# yarns_v03.net
KiCad netlist of a schematic drawn in EAGLE
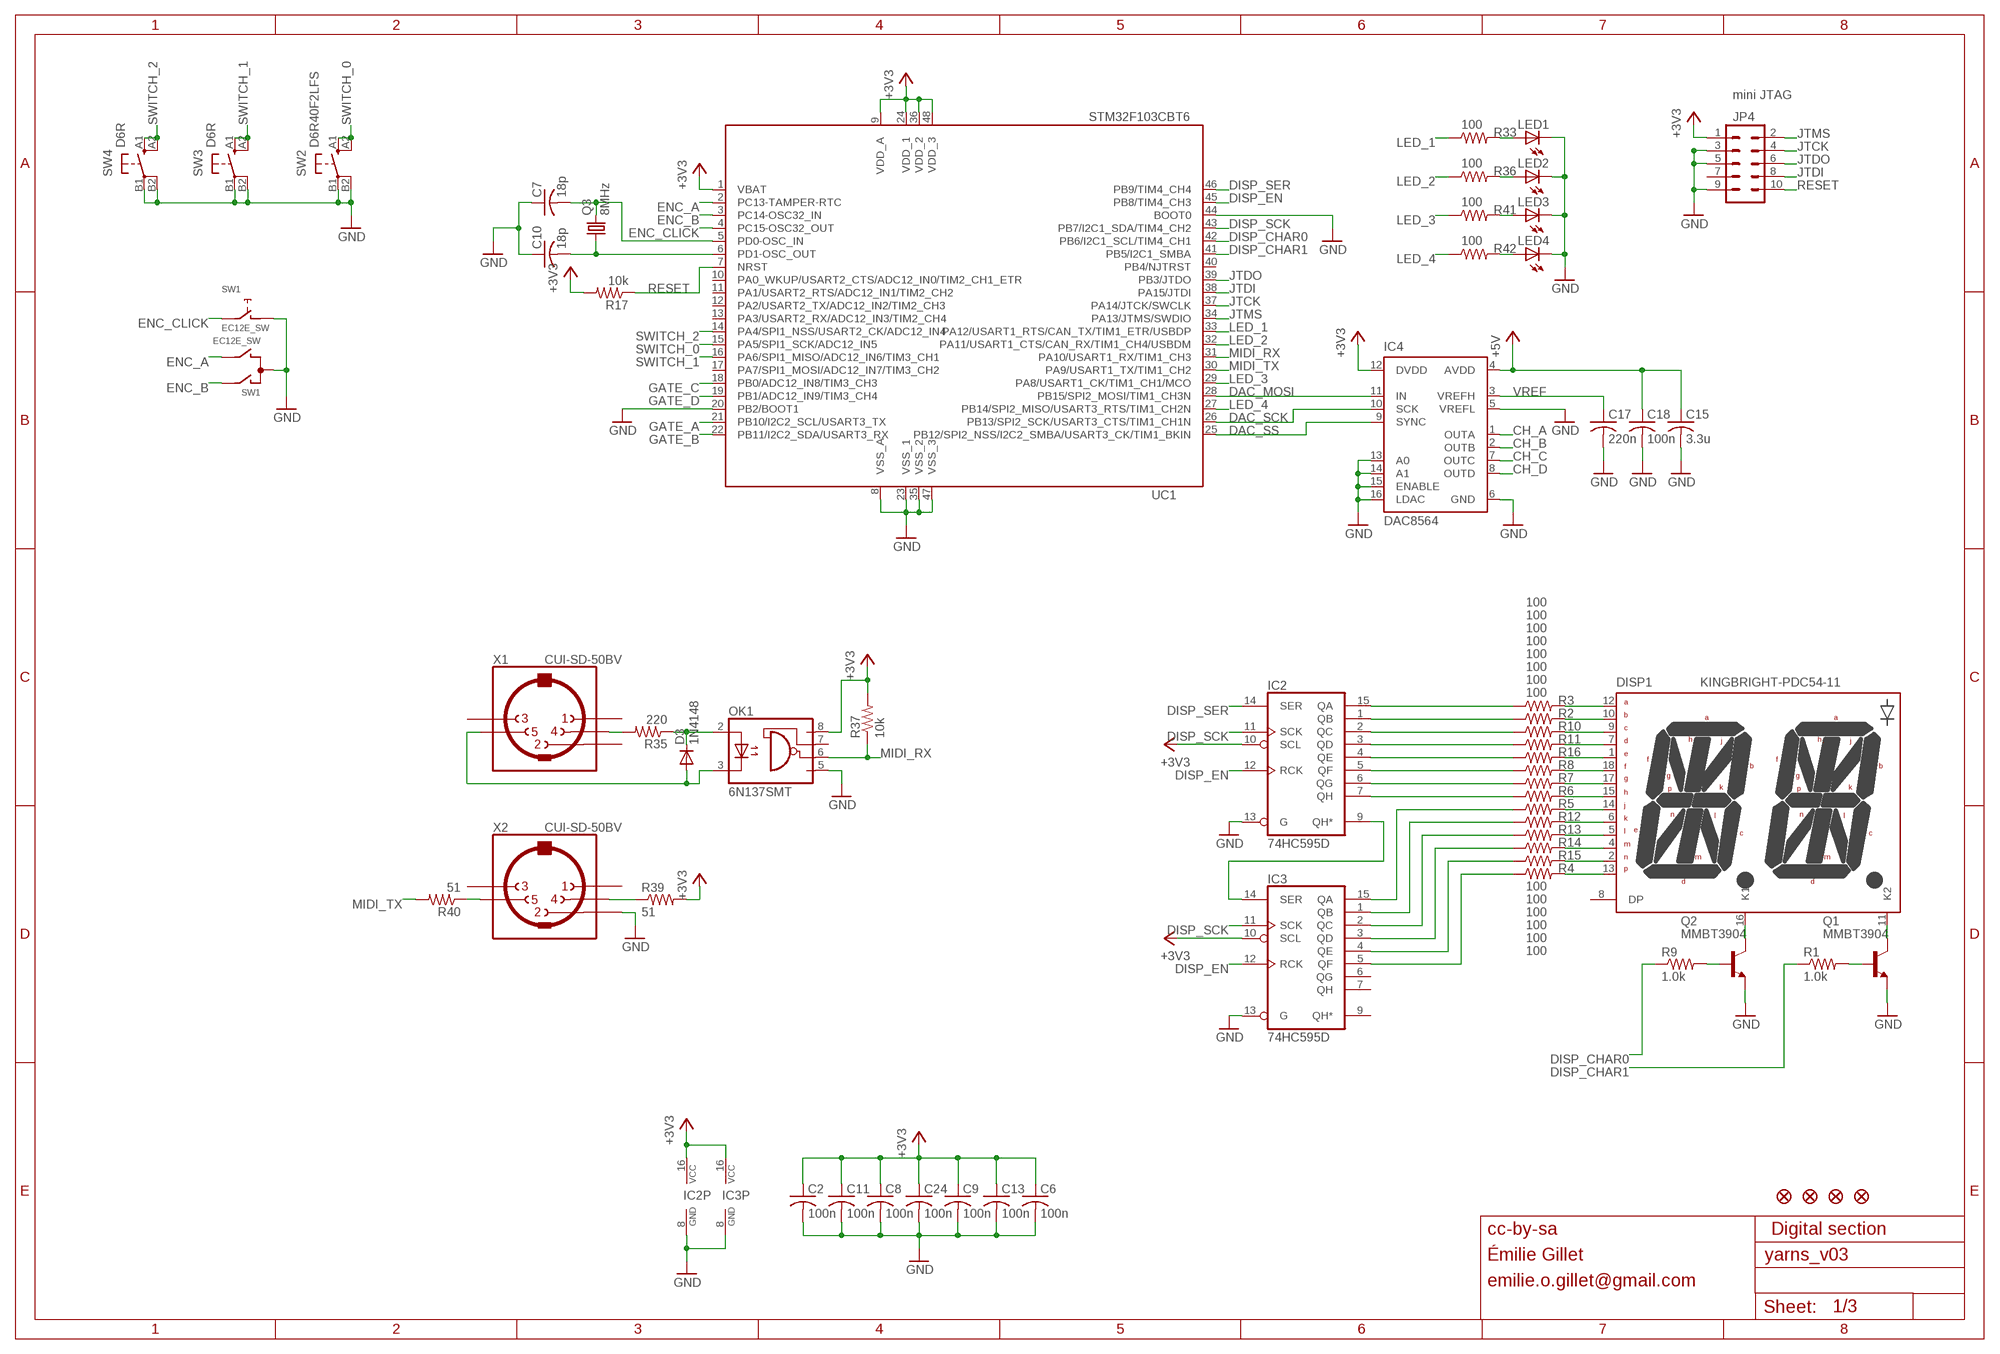
[diagram p0: schematic, sheet 1]
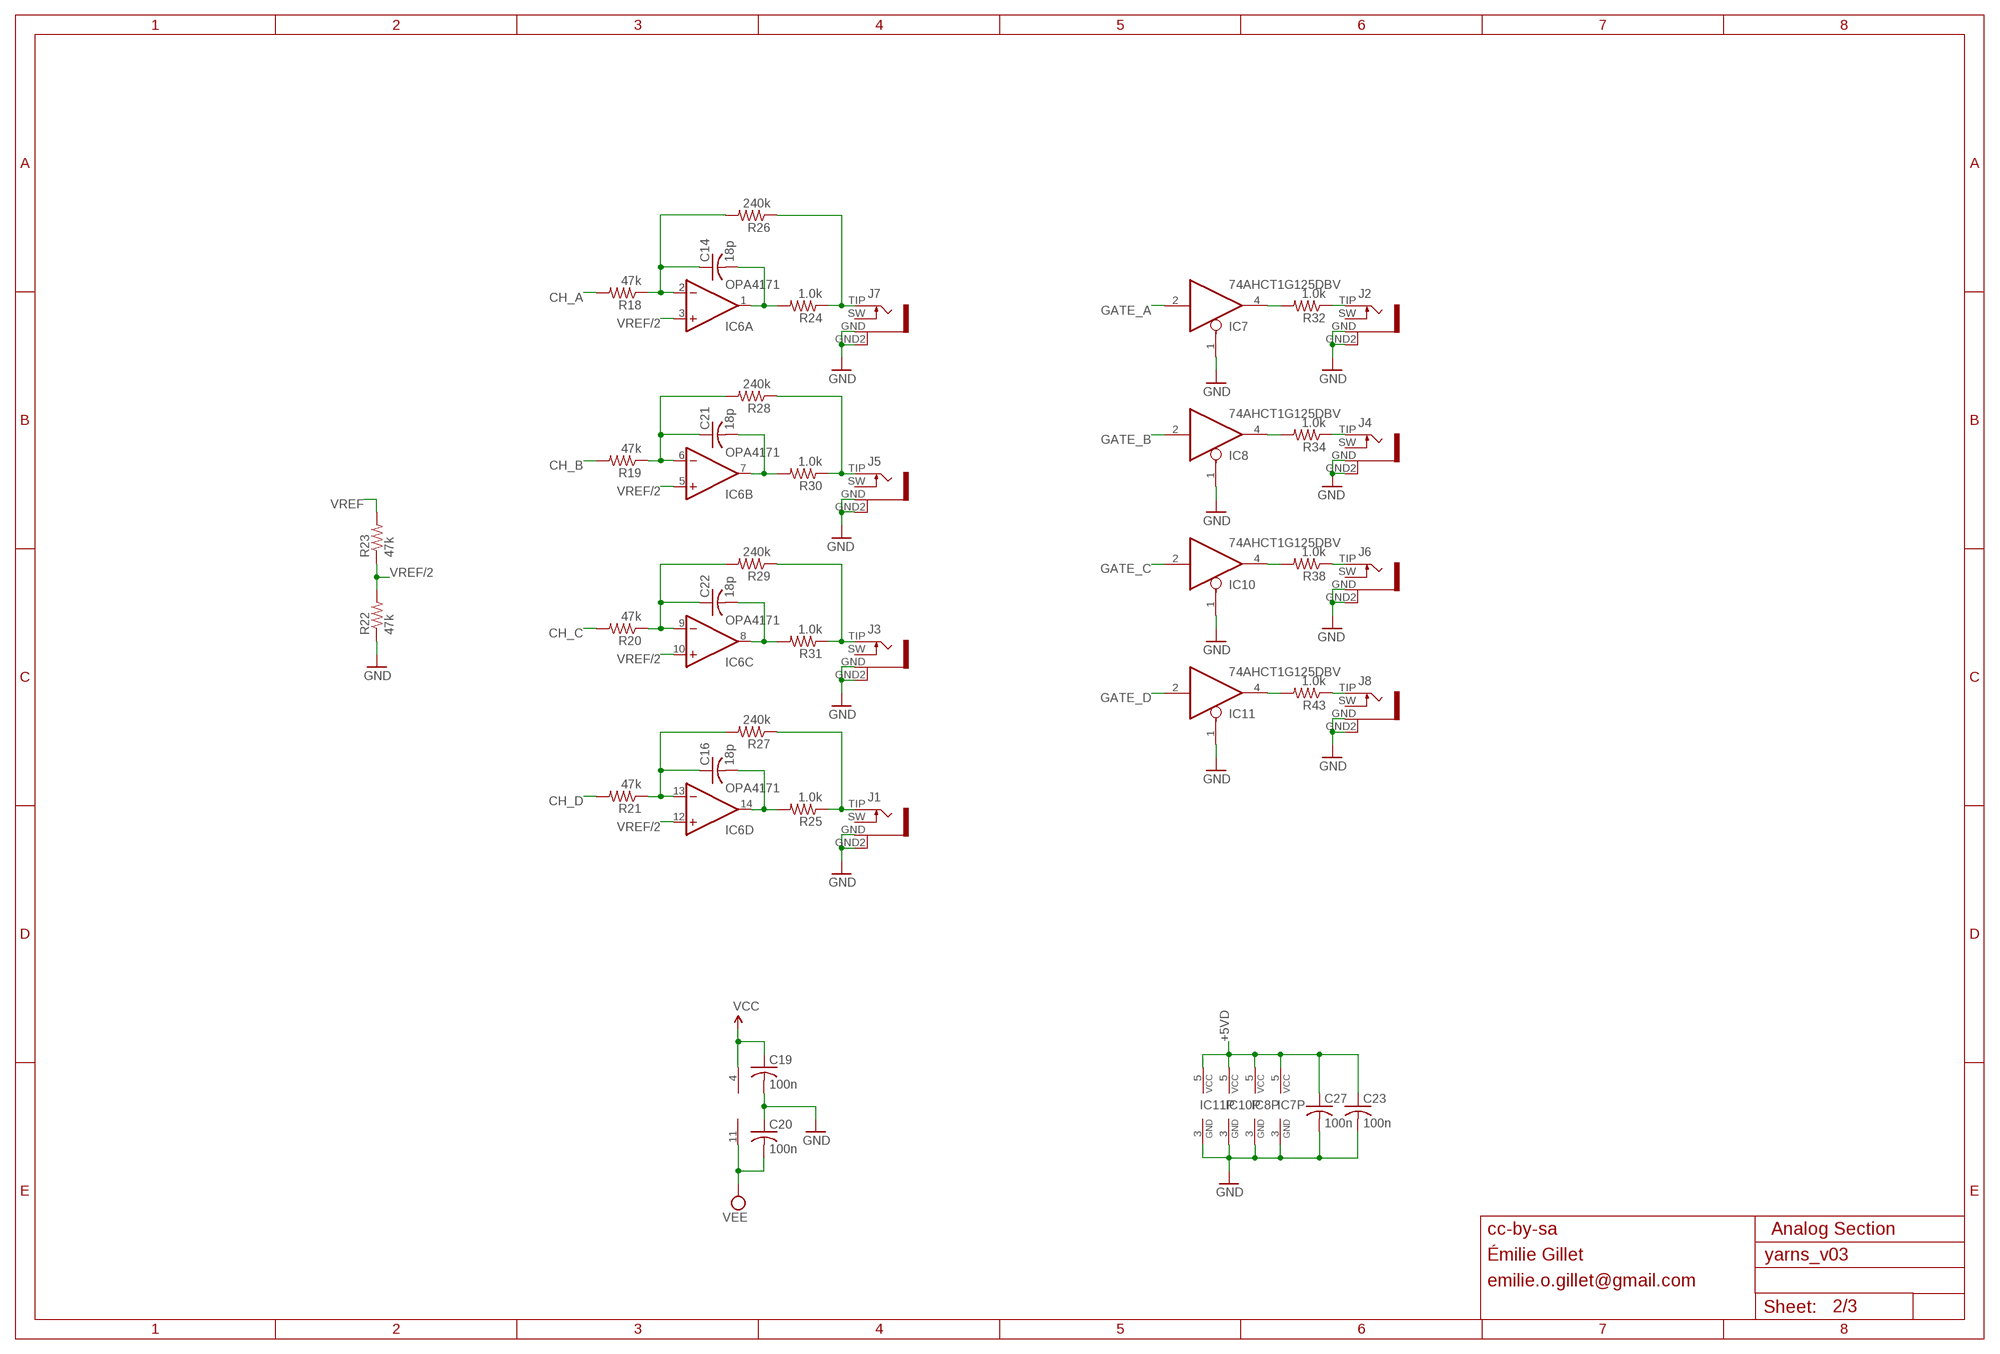
[diagram p1: schematic, sheet 2]
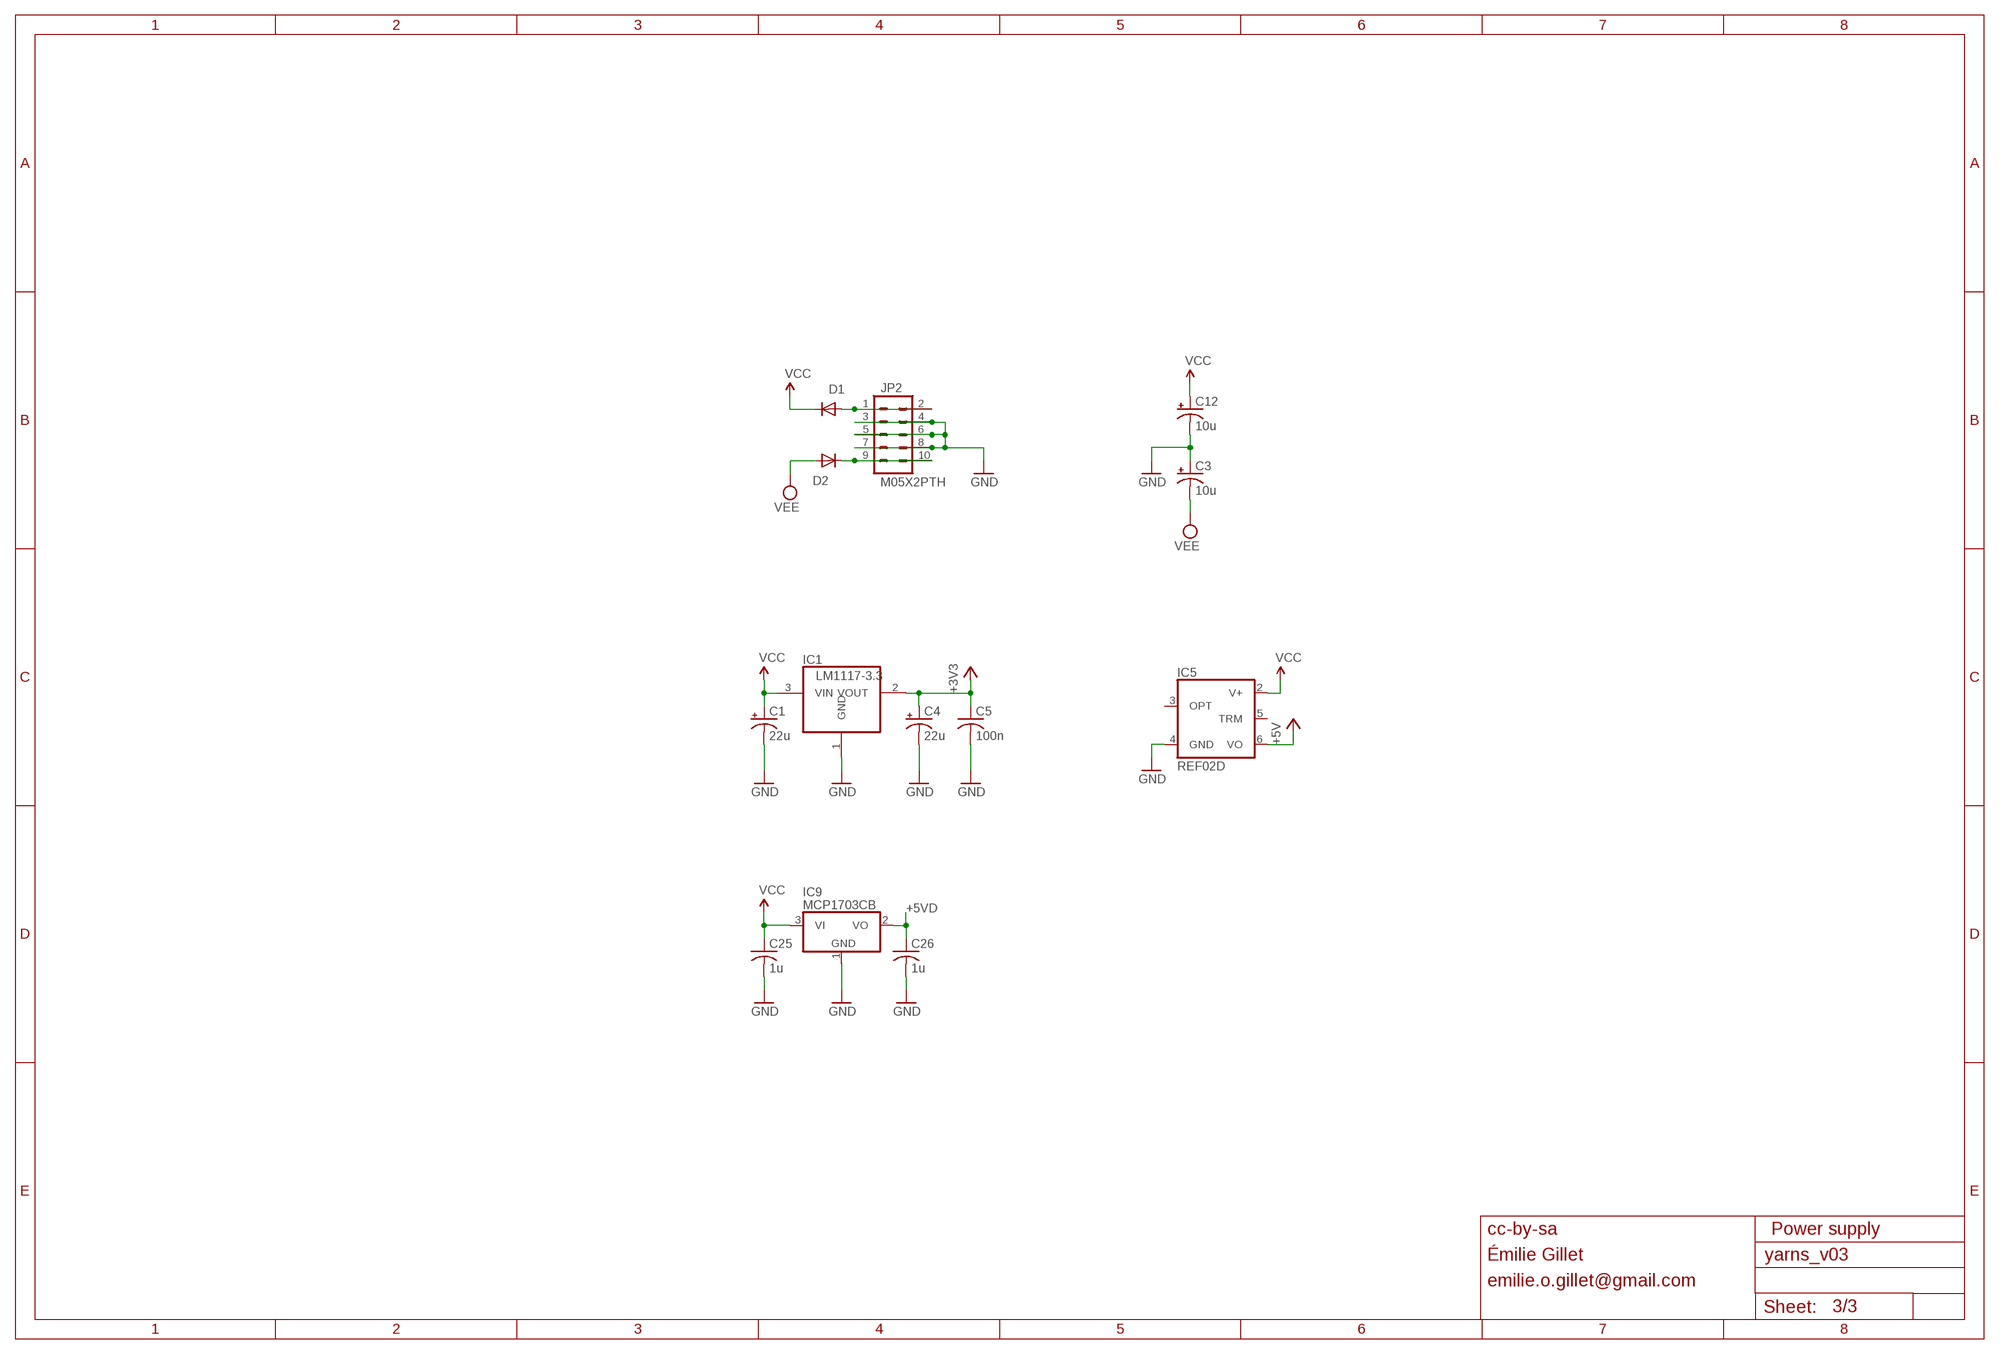
[diagram p2: schematic, sheet 3]

(export (version "E")
  (design (tool "Eeschema 10.0.6"))
  (components
    (comp (ref "C1")
      (value "22u")
      (footprint "eagle-import:PANASONIC_C")
      (libsource (lib "eagle-import") (part "CPOL-USC"))
    )
    (comp (ref "C3")
      (value "10u")
      (footprint "eagle-import:PANASONIC_A")
      (libsource (lib "eagle-import") (part "CPOL-USA"))
    )
    (comp (ref "C4")
      (value "22u")
      (footprint "eagle-import:PANASONIC_C")
      (libsource (lib "eagle-import") (part "CPOL-USC"))
    )
    (comp (ref "C5")
      (value "100n")
      (footprint "eagle-import:C0603")
      (libsource (lib "eagle-import") (part "C-USC0603"))
    )
    (comp (ref "C12")
      (value "10u")
      (footprint "eagle-import:PANASONIC_A")
      (libsource (lib "eagle-import") (part "CPOL-USA"))
    )
    (comp (ref "C25")
      (value "1u")
      (footprint "eagle-import:C0603")
      (libsource (lib "eagle-import") (part "C-USC0603"))
    )
    (comp (ref "C26")
      (value "1u")
      (footprint "eagle-import:C0603")
      (libsource (lib "eagle-import") (part "C-USC0603"))
    )
    (comp (ref "D1")
      (value "1N5819HW")
      (footprint "eagle-import:SOD123")
      (libsource (lib "eagle-import") (part "DIODE-SOD123"))
    )
    (comp (ref "D2")
      (value "1N5819HW")
      (footprint "eagle-import:SOD123")
      (libsource (lib "eagle-import") (part "DIODE-SOD123"))
    )
    (comp (ref "IC1")
      (value "LM1117-3.3")
      (footprint "eagle-import:SOT223")
      (libsource (lib "eagle-import") (part "REG1117"))
    )
    (comp (ref "IC5")
      (value "REF02D")
      (footprint "eagle-import:SO08")
      (libsource (lib "eagle-import") (part "REF02D"))
    )
    (comp (ref "IC9")
      (value "MCP1703CB")
      (footprint "eagle-import:SOT23")
      (libsource (lib "eagle-import") (part "MCP1703CB"))
    )
    (comp (ref "JP2")
      (value "M05X2PTH")
      (footprint "eagle-import:AVR_ICSP")
      (libsource (lib "eagle-import") (part "M05X2PTH"))
    )
    (comp (ref "C2")
      (value "100n")
      (footprint "eagle-import:C0603")
      (libsource (lib "eagle-import") (part "C-USC0603"))
    )
    (comp (ref "C6")
      (value "100n")
      (footprint "eagle-import:C0603")
      (libsource (lib "eagle-import") (part "C-USC0603"))
    )
    (comp (ref "C7")
      (value "18p")
      (footprint "eagle-import:C0603")
      (libsource (lib "eagle-import") (part "C-USC0603"))
    )
    (comp (ref "C8")
      (value "100n")
      (footprint "eagle-import:C0603")
      (libsource (lib "eagle-import") (part "C-USC0603"))
    )
    (comp (ref "C9")
      (value "100n")
      (footprint "eagle-import:C0603")
      (libsource (lib "eagle-import") (part "C-USC0603"))
    )
    (comp (ref "C10")
      (value "18p")
      (footprint "eagle-import:C0603")
      (libsource (lib "eagle-import") (part "C-USC0603"))
    )
    (comp (ref "C11")
      (value "100n")
      (footprint "eagle-import:C0603")
      (libsource (lib "eagle-import") (part "C-USC0603"))
    )
    (comp (ref "C13")
      (value "100n")
      (footprint "eagle-import:C0603")
      (libsource (lib "eagle-import") (part "C-USC0603"))
    )
    (comp (ref "C15")
      (value "3.3u")
      (footprint "eagle-import:C0603")
      (libsource (lib "eagle-import") (part "C-USC0603"))
    )
    (comp (ref "C17")
      (value "220n")
      (footprint "eagle-import:C0603")
      (libsource (lib "eagle-import") (part "C-USC0603"))
    )
    (comp (ref "C18")
      (value "100n")
      (footprint "eagle-import:C0603")
      (libsource (lib "eagle-import") (part "C-USC0603"))
    )
    (comp (ref "C24")
      (value "100n")
      (footprint "eagle-import:C0603")
      (libsource (lib "eagle-import") (part "C-USC0603"))
    )
    (comp (ref "D3")
      (value "1N4148")
      (footprint "eagle-import:SOD323-W")
      (libsource (lib "eagle-import") (part "DIODE-SOD323-W"))
    )
    (comp (ref "DISP1")
      (value "KINGBRIGHT-PDC54-11")
      (footprint "eagle-import:PDC54")
      (libsource (lib "eagle-import") (part "KINGBRIGHT-PDC54-11"))
    )
    (comp (ref "F1")
      (value "FIDUCIAL1X2")
      (footprint "eagle-import:FIDUCIAL-1X2")
      (libsource (lib "eagle-import") (part "FIDUCIAL1X2"))
    )
    (comp (ref "F3")
      (value "FIDUCIAL1X2")
      (footprint "eagle-import:FIDUCIAL-1X2")
      (libsource (lib "eagle-import") (part "FIDUCIAL1X2"))
    )
    (comp (ref "F5")
      (value "FIDUCIAL1X2")
      (footprint "eagle-import:FIDUCIAL-1X2")
      (libsource (lib "eagle-import") (part "FIDUCIAL1X2"))
    )
    (comp (ref "F6")
      (value "FIDUCIAL1X2")
      (footprint "eagle-import:FIDUCIAL-1X2")
      (libsource (lib "eagle-import") (part "FIDUCIAL1X2"))
    )
    (comp (ref "IC2")
      (value "74HC595D")
      (footprint "eagle-import:SO16")
      (libsource (lib "eagle-import") (part "74595DHC"))
    )
    (comp (ref "IC3")
      (value "74HC595D")
      (footprint "eagle-import:SO16")
      (libsource (lib "eagle-import") (part "74595DHC"))
    )
    (comp (ref "IC4")
      (value "DAC8564")
      (footprint "eagle-import:SOP65P640X110-16N")
      (libsource (lib "eagle-import") (part "DAC8564"))
    )
    (comp (ref "JP4")
      (value "M05X2MINIJTAG")
      (footprint "eagle-import:2X5-1.27")
      (libsource (lib "eagle-import") (part "M05X2MINIJTAG"))
    )
    (comp (ref "LED1")
      (value "LED3MM")
      (footprint "eagle-import:LED3MM")
      (libsource (lib "eagle-import") (part "LED3MM"))
    )
    (comp (ref "LED2")
      (value "LED3MM")
      (footprint "eagle-import:LED3MM")
      (libsource (lib "eagle-import") (part "LED3MM"))
    )
    (comp (ref "LED3")
      (value "LED3MM")
      (footprint "eagle-import:LED3MM")
      (libsource (lib "eagle-import") (part "LED3MM"))
    )
    (comp (ref "LED4")
      (value "LED3MM")
      (footprint "eagle-import:LED3MM")
      (libsource (lib "eagle-import") (part "LED3MM"))
    )
    (comp (ref "OK1")
      (value "6N137SMT")
      (footprint "eagle-import:DIL8-SMD")
      (libsource (lib "eagle-import") (part "6N137SMT"))
    )
    (comp (ref "Q1")
      (value "MMBT3904")
      (footprint "eagle-import:SOT23-BEC")
      (libsource (lib "eagle-import") (part "-NPN-SOT23-BECMMBT3904LT1"))
    )
    (comp (ref "Q2")
      (value "MMBT3904")
      (footprint "eagle-import:SOT23-BEC")
      (libsource (lib "eagle-import") (part "-NPN-SOT23-BECMMBT3904LT1"))
    )
    (comp (ref "Q3")
      (value "8MHz")
      (footprint "eagle-import:HC49UP")
      (libsource (lib "eagle-import") (part "CRYSTALHC49UP"))
    )
    (comp (ref "R1")
      (value "1.0k")
      (footprint "eagle-import:R0603")
      (libsource (lib "eagle-import") (part "R-US_R0603"))
    )
    (comp (ref "R2")
      (value "100")
      (footprint "eagle-import:R0603")
      (libsource (lib "eagle-import") (part "R-US_R0603"))
    )
    (comp (ref "R3")
      (value "100")
      (footprint "eagle-import:R0603")
      (libsource (lib "eagle-import") (part "R-US_R0603"))
    )
    (comp (ref "R4")
      (value "100")
      (footprint "eagle-import:R0603")
      (libsource (lib "eagle-import") (part "R-US_R0603"))
    )
    (comp (ref "R5")
      (value "100")
      (footprint "eagle-import:R0603")
      (libsource (lib "eagle-import") (part "R-US_R0603"))
    )
    (comp (ref "R6")
      (value "100")
      (footprint "eagle-import:R0603")
      (libsource (lib "eagle-import") (part "R-US_R0603"))
    )
    (comp (ref "R7")
      (value "100")
      (footprint "eagle-import:R0603")
      (libsource (lib "eagle-import") (part "R-US_R0603"))
    )
    (comp (ref "R8")
      (value "100")
      (footprint "eagle-import:R0603")
      (libsource (lib "eagle-import") (part "R-US_R0603"))
    )
    (comp (ref "R9")
      (value "1.0k")
      (footprint "eagle-import:R0603")
      (libsource (lib "eagle-import") (part "R-US_R0603"))
    )
    (comp (ref "R10")
      (value "100")
      (footprint "eagle-import:R0603")
      (libsource (lib "eagle-import") (part "R-US_R0603"))
    )
    (comp (ref "R11")
      (value "100")
      (footprint "eagle-import:R0603")
      (libsource (lib "eagle-import") (part "R-US_R0603"))
    )
    (comp (ref "R12")
      (value "100")
      (footprint "eagle-import:R0603")
      (libsource (lib "eagle-import") (part "R-US_R0603"))
    )
    (comp (ref "R13")
      (value "100")
      (footprint "eagle-import:R0603")
      (libsource (lib "eagle-import") (part "R-US_R0603"))
    )
    (comp (ref "R14")
      (value "100")
      (footprint "eagle-import:R0603")
      (libsource (lib "eagle-import") (part "R-US_R0603"))
    )
    (comp (ref "R15")
      (value "100")
      (footprint "eagle-import:R0603")
      (libsource (lib "eagle-import") (part "R-US_R0603"))
    )
    (comp (ref "R16")
      (value "100")
      (footprint "eagle-import:R0603")
      (libsource (lib "eagle-import") (part "R-US_R0603"))
    )
    (comp (ref "R17")
      (value "10k")
      (footprint "eagle-import:R0603")
      (libsource (lib "eagle-import") (part "R-US_R0603"))
    )
    (comp (ref "R33")
      (value "100")
      (footprint "eagle-import:R0603")
      (libsource (lib "eagle-import") (part "R-US_R0603"))
    )
    (comp (ref "R35")
      (value "220")
      (footprint "eagle-import:R0603")
      (libsource (lib "eagle-import") (part "R-US_R0603"))
    )
    (comp (ref "R36")
      (value "100")
      (footprint "eagle-import:R0603")
      (libsource (lib "eagle-import") (part "R-US_R0603"))
    )
    (comp (ref "R37")
      (value "10k")
      (footprint "eagle-import:R0603")
      (libsource (lib "eagle-import") (part "R-US_R0603"))
    )
    (comp (ref "R39")
      (value "51")
      (footprint "eagle-import:R0603")
      (libsource (lib "eagle-import") (part "R-US_R0603"))
    )
    (comp (ref "R40")
      (value "51")
      (footprint "eagle-import:R0603")
      (libsource (lib "eagle-import") (part "R-US_R0603"))
    )
    (comp (ref "R41")
      (value "100")
      (footprint "eagle-import:R0603")
      (libsource (lib "eagle-import") (part "R-US_R0603"))
    )
    (comp (ref "R42")
      (value "100")
      (footprint "eagle-import:R0603")
      (libsource (lib "eagle-import") (part "R-US_R0603"))
    )
    (comp (ref "SW1")
      (value "EC12E_SW")
      (footprint "eagle-import:ALPS_EC12E_SW")
      (libsource (lib "eagle-import") (part "EC12E_SW"))
    )
    (comp (ref "SW2")
      (value "D6R40F2LFS")
      (footprint "eagle-import:D6R")
      (libsource (lib "eagle-import") (part "D6R"))
    )
    (comp (ref "SW3")
      (value "D6R")
      (footprint "eagle-import:D6R")
      (libsource (lib "eagle-import") (part "D6R"))
    )
    (comp (ref "SW4")
      (value "D6R")
      (footprint "eagle-import:D6R")
      (libsource (lib "eagle-import") (part "D6R"))
    )
    (comp (ref "UC1")
      (value "STM32F103CBT6")
      (footprint "eagle-import:LQFP48")
      (libsource (lib "eagle-import") (part "STM32F103CB"))
    )
    (comp (ref "X1")
      (value "CUI-SD-50BV")
      (footprint "eagle-import:SD-50BV")
      (libsource (lib "eagle-import") (part "MAB5SHCUI-SD-50BV"))
    )
    (comp (ref "X2")
      (value "CUI-SD-50BV")
      (footprint "eagle-import:SD-50BV")
      (libsource (lib "eagle-import") (part "MAB5SHCUI-SD-50BV"))
    )
    (comp (ref "C14")
      (value "18p")
      (footprint "eagle-import:C0603")
      (libsource (lib "eagle-import") (part "C-USC0603"))
    )
    (comp (ref "C16")
      (value "18p")
      (footprint "eagle-import:C0603")
      (libsource (lib "eagle-import") (part "C-USC0603"))
    )
    (comp (ref "C19")
      (value "100n")
      (footprint "eagle-import:C0603")
      (libsource (lib "eagle-import") (part "C-USC0603"))
    )
    (comp (ref "C20")
      (value "100n")
      (footprint "eagle-import:C0603")
      (libsource (lib "eagle-import") (part "C-USC0603"))
    )
    (comp (ref "C21")
      (value "18p")
      (footprint "eagle-import:C0603")
      (libsource (lib "eagle-import") (part "C-USC0603"))
    )
    (comp (ref "C22")
      (value "18p")
      (footprint "eagle-import:C0603")
      (libsource (lib "eagle-import") (part "C-USC0603"))
    )
    (comp (ref "C23")
      (value "100n")
      (footprint "eagle-import:C0603")
      (libsource (lib "eagle-import") (part "C-USC0603"))
    )
    (comp (ref "C27")
      (value "100n")
      (footprint "eagle-import:C0603")
      (libsource (lib "eagle-import") (part "C-USC0603"))
    )
    (comp (ref "IC6")
      (value "OPA4171")
      (footprint "eagle-import:SO14")
      (libsource (lib "eagle-import") (part "TL074D"))
    )
    (comp (ref "IC7")
      (value "74AHCT1G125DBV")
      (footprint "eagle-import:SOT23-5")
      (libsource (lib "eagle-import") (part "741G125DBVAHCT"))
    )
    (comp (ref "IC8")
      (value "74AHCT1G125DBV")
      (footprint "eagle-import:SOT23-5")
      (libsource (lib "eagle-import") (part "741G125DBVAHCT"))
    )
    (comp (ref "IC10")
      (value "74AHCT1G125DBV")
      (footprint "eagle-import:SOT23-5")
      (libsource (lib "eagle-import") (part "741G125DBVAHCT"))
    )
    (comp (ref "IC11")
      (value "74AHCT1G125DBV")
      (footprint "eagle-import:SOT23-5")
      (libsource (lib "eagle-import") (part "741G125DBVAHCT"))
    )
    (comp (ref "J1")
      (value "PJ301WQP")
      (footprint "eagle-import:WQP_PJ_301BM")
      (libsource (lib "eagle-import") (part "PJ301WQP"))
    )
    (comp (ref "J2")
      (value "PJ301WQP")
      (footprint "eagle-import:WQP_PJ_301BM")
      (libsource (lib "eagle-import") (part "PJ301WQP"))
    )
    (comp (ref "J3")
      (value "PJ301WQP")
      (footprint "eagle-import:WQP_PJ_301BM")
      (libsource (lib "eagle-import") (part "PJ301WQP"))
    )
    (comp (ref "J4")
      (value "PJ301WQP")
      (footprint "eagle-import:WQP_PJ_301BM")
      (libsource (lib "eagle-import") (part "PJ301WQP"))
    )
    (comp (ref "J5")
      (value "PJ301WQP")
      (footprint "eagle-import:WQP_PJ_301BM")
      (libsource (lib "eagle-import") (part "PJ301WQP"))
    )
    (comp (ref "J6")
      (value "PJ301WQP")
      (footprint "eagle-import:WQP_PJ_301BM")
      (libsource (lib "eagle-import") (part "PJ301WQP"))
    )
    (comp (ref "J7")
      (value "PJ301WQP")
      (footprint "eagle-import:WQP_PJ_301BM")
      (libsource (lib "eagle-import") (part "PJ301WQP"))
    )
    (comp (ref "J8")
      (value "PJ301WQP")
      (footprint "eagle-import:WQP_PJ_301BM")
      (libsource (lib "eagle-import") (part "PJ301WQP"))
    )
    (comp (ref "R18")
      (value "47k")
      (footprint "eagle-import:R0603")
      (libsource (lib "eagle-import") (part "R-US_R0603"))
    )
    (comp (ref "R19")
      (value "47k")
      (footprint "eagle-import:R0603")
      (libsource (lib "eagle-import") (part "R-US_R0603"))
    )
    (comp (ref "R20")
      (value "47k")
      (footprint "eagle-import:R0603")
      (libsource (lib "eagle-import") (part "R-US_R0603"))
    )
    (comp (ref "R21")
      (value "47k")
      (footprint "eagle-import:R0603")
      (libsource (lib "eagle-import") (part "R-US_R0603"))
    )
    (comp (ref "R22")
      (value "47k")
      (footprint "eagle-import:R0603")
      (libsource (lib "eagle-import") (part "R-US_R0603"))
    )
    (comp (ref "R23")
      (value "47k")
      (footprint "eagle-import:R0603")
      (libsource (lib "eagle-import") (part "R-US_R0603"))
    )
    (comp (ref "R24")
      (value "1.0k")
      (footprint "eagle-import:R0603")
      (libsource (lib "eagle-import") (part "R-US_R0603"))
    )
    (comp (ref "R25")
      (value "1.0k")
      (footprint "eagle-import:R0603")
      (libsource (lib "eagle-import") (part "R-US_R0603"))
    )
    (comp (ref "R26")
      (value "240k")
      (footprint "eagle-import:R0603")
      (libsource (lib "eagle-import") (part "R-US_R0603"))
    )
    (comp (ref "R27")
      (value "240k")
      (footprint "eagle-import:R0603")
      (libsource (lib "eagle-import") (part "R-US_R0603"))
    )
    (comp (ref "R28")
      (value "240k")
      (footprint "eagle-import:R0603")
      (libsource (lib "eagle-import") (part "R-US_R0603"))
    )
    (comp (ref "R29")
      (value "240k")
      (footprint "eagle-import:R0603")
      (libsource (lib "eagle-import") (part "R-US_R0603"))
    )
    (comp (ref "R30")
      (value "1.0k")
      (footprint "eagle-import:R0603")
      (libsource (lib "eagle-import") (part "R-US_R0603"))
    )
    (comp (ref "R31")
      (value "1.0k")
      (footprint "eagle-import:R0603")
      (libsource (lib "eagle-import") (part "R-US_R0603"))
    )
    (comp (ref "R32")
      (value "1.0k")
      (footprint "eagle-import:R0603")
      (libsource (lib "eagle-import") (part "R-US_R0603"))
    )
    (comp (ref "R34")
      (value "1.0k")
      (footprint "eagle-import:R0603")
      (libsource (lib "eagle-import") (part "R-US_R0603"))
    )
    (comp (ref "R38")
      (value "1.0k")
      (footprint "eagle-import:R0603")
      (libsource (lib "eagle-import") (part "R-US_R0603"))
    )
    (comp (ref "R43")
      (value "1.0k")
      (footprint "eagle-import:R0603")
      (libsource (lib "eagle-import") (part "R-US_R0603"))
    )
  )
  (nets
    (net (code "1") (name "+3V3") (class "Default")
      (node (ref "C11") (pin "1") (pinfunction "1_1") (pintype "passive"))
      (node (ref "C13") (pin "1") (pinfunction "1_1") (pintype "passive"))
      (node (ref "C2") (pin "1") (pinfunction "1_1") (pintype "passive"))
      (node (ref "C24") (pin "1") (pinfunction "1_1") (pintype "passive"))
      (node (ref "C4") (pin "+") (pinfunction "+_+") (pintype "passive"))
      (node (ref "C5") (pin "1") (pinfunction "1_1") (pintype "passive"))
      (node (ref "C6") (pin "1") (pinfunction "1_1") (pintype "passive"))
      (node (ref "C8") (pin "1") (pinfunction "1_1") (pintype "passive"))
      (node (ref "C9") (pin "1") (pinfunction "1_1") (pintype "passive"))
      (node (ref "IC1") (pin "2") (pinfunction "VOUT_2") (pintype "output"))
      (node (ref "IC2") (pin "10") (pinfunction "SCL_10") (pintype "input"))
      (node (ref "IC2") (pin "16") (pinfunction "VCC_16") (pintype "power_in"))
      (node (ref "IC3") (pin "10") (pinfunction "SCL_10") (pintype "input"))
      (node (ref "IC3") (pin "16") (pinfunction "VCC_16") (pintype "power_in"))
      (node (ref "IC4") (pin "12") (pinfunction "DVDD_12") (pintype "power_in"))
      (node (ref "JP4") (pin "1") (pinfunction "1_1") (pintype "passive"))
      (node (ref "OK1") (pin "8") (pinfunction "VCC_8") (pintype "passive"))
      (node (ref "R17") (pin "2") (pinfunction "2_2") (pintype "passive"))
      (node (ref "R37") (pin "2") (pinfunction "2_2") (pintype "passive"))
      (node (ref "R39") (pin "2") (pinfunction "2_2") (pintype "passive"))
      (node (ref "UC1") (pin "1") (pinfunction "VBAT_1") (pintype "power_in"))
      (node (ref "UC1") (pin "24") (pinfunction "VDD_1_24") (pintype "power_in"))
      (node (ref "UC1") (pin "36") (pinfunction "VDD_2_36") (pintype "power_in"))
      (node (ref "UC1") (pin "48") (pinfunction "VDD_3_48") (pintype "power_in"))
      (node (ref "UC1") (pin "9") (pinfunction "VDD_A_9") (pintype "power_in"))
    )
    (net (code "2") (name "+5V") (class "Default")
      (node (ref "C15") (pin "1") (pinfunction "1_1") (pintype "passive"))
      (node (ref "C18") (pin "1") (pinfunction "1_1") (pintype "passive"))
      (node (ref "IC4") (pin "4") (pinfunction "AVDD_4") (pintype "power_in"))
      (node (ref "IC5") (pin "6") (pinfunction "VO_6") (pintype "output"))
    )
    (net (code "3") (name "+5VD") (class "Default")
      (node (ref "C23") (pin "1") (pinfunction "1_1") (pintype "passive"))
      (node (ref "C26") (pin "1") (pinfunction "1_1") (pintype "passive"))
      (node (ref "C27") (pin "1") (pinfunction "1_1") (pintype "passive"))
      (node (ref "IC10") (pin "5") (pinfunction "VCC_5") (pintype "power_in"))
      (node (ref "IC11") (pin "5") (pinfunction "VCC_5") (pintype "power_in"))
      (node (ref "IC7") (pin "5") (pinfunction "VCC_5") (pintype "power_in"))
      (node (ref "IC8") (pin "5") (pinfunction "VCC_5") (pintype "power_in"))
      (node (ref "IC9") (pin "2") (pinfunction "VO_2") (pintype "passive"))
    )
    (net (code "4") (name "CH_A") (class "Default")
      (node (ref "IC4") (pin "1") (pinfunction "OUTA_1") (pintype "output"))
      (node (ref "R18") (pin "2") (pinfunction "2_2") (pintype "passive"))
    )
    (net (code "5") (name "CH_B") (class "Default")
      (node (ref "IC4") (pin "2") (pinfunction "OUTB_2") (pintype "output"))
      (node (ref "R19") (pin "2") (pinfunction "2_2") (pintype "passive"))
    )
    (net (code "6") (name "CH_C") (class "Default")
      (node (ref "IC4") (pin "7") (pinfunction "OUTC_7") (pintype "output"))
      (node (ref "R20") (pin "2") (pinfunction "2_2") (pintype "passive"))
    )
    (net (code "7") (name "CH_D") (class "Default")
      (node (ref "IC4") (pin "8") (pinfunction "OUTD_8") (pintype "output"))
      (node (ref "R21") (pin "2") (pinfunction "2_2") (pintype "passive"))
    )
    (net (code "8") (name "DAC_MOSI") (class "Default")
      (node (ref "IC4") (pin "11") (pinfunction "IN_11") (pintype "input"))
      (node (ref "UC1") (pin "28") (pinfunction "PB15/SPI2_MOSI/TIM1_CH3N_28") (pintype "input"))
    )
    (net (code "9") (name "DAC_SCK") (class "Default")
      (node (ref "IC4") (pin "10") (pinfunction "SCK_10") (pintype "input"))
      (node (ref "UC1") (pin "26") (pinfunction "PB13/SPI2_SCK/USART3_CTS/TIM1_CH1N_26") (pintype "input"))
    )
    (net (code "10") (name "DAC_SS") (class "Default")
      (node (ref "IC4") (pin "9") (pinfunction "SYNC_9") (pintype "input"))
      (node (ref "UC1") (pin "25") (pinfunction "PB12/SPI2_NSS/I2C2_SMBA/USART3_CK/TIM1_BKIN_25") (pintype "input"))
    )
    (net (code "11") (name "DISP_CHAR0") (class "Default")
      (node (ref "R9") (pin "1") (pinfunction "1_1") (pintype "passive"))
      (node (ref "UC1") (pin "42") (pinfunction "PB6/I2C1_SCL/TIM4_CH1_42") (pintype "input"))
    )
    (net (code "12") (name "DISP_CHAR1") (class "Default")
      (node (ref "R1") (pin "1") (pinfunction "1_1") (pintype "passive"))
      (node (ref "UC1") (pin "41") (pinfunction "PB5/I2C1_SMBA_41") (pintype "input"))
    )
    (net (code "13") (name "DISP_EN") (class "Default")
      (node (ref "IC2") (pin "12") (pinfunction "RCK_12") (pintype "input"))
      (node (ref "IC3") (pin "12") (pinfunction "RCK_12") (pintype "input"))
      (node (ref "UC1") (pin "45") (pinfunction "PB8/TIM4_CH3_45") (pintype "bidirectional"))
    )
    (net (code "14") (name "DISP_SCK") (class "Default")
      (node (ref "IC2") (pin "11") (pinfunction "SCK_11") (pintype "input"))
      (node (ref "IC3") (pin "11") (pinfunction "SCK_11") (pintype "input"))
      (node (ref "UC1") (pin "43") (pinfunction "PB7/I2C1_SDA/TIM4_CH2_43") (pintype "bidirectional"))
    )
    (net (code "15") (name "DISP_SER") (class "Default")
      (node (ref "IC2") (pin "14") (pinfunction "SER_14") (pintype "input"))
      (node (ref "UC1") (pin "46") (pinfunction "PB9/TIM4_CH4_46") (pintype "input"))
    )
    (net (code "16") (name "ENC_A") (class "Default")
      (node (ref "SW1") (pin "B") (pinfunction "B_B") (pintype "passive"))
      (node (ref "UC1") (pin "2") (pinfunction "PC13-TAMPER-RTC_2") (pintype "input"))
    )
    (net (code "17") (name "ENC_B") (class "Default")
      (node (ref "SW1") (pin "A") (pinfunction "A_A") (pintype "passive"))
      (node (ref "UC1") (pin "3") (pinfunction "PC14-OSC32_IN_3") (pintype "input"))
    )
    (net (code "18") (name "ENC_CLICK") (class "Default")
      (node (ref "SW1") (pin "E") (pinfunction "2_E") (pintype "passive"))
      (node (ref "UC1") (pin "4") (pinfunction "PC15-OSC32_OUT_4") (pintype "input"))
    )
    (net (code "19") (name "GATE_A") (class "Default")
      (node (ref "IC7") (pin "2") (pinfunction "I_2") (pintype "input"))
      (node (ref "UC1") (pin "21") (pinfunction "PB10/I2C2_SCL/USART3_TX_21") (pintype "input"))
    )
    (net (code "20") (name "GATE_B") (class "Default")
      (node (ref "IC8") (pin "2") (pinfunction "I_2") (pintype "input"))
      (node (ref "UC1") (pin "22") (pinfunction "PB11/I2C2_SDA/USART3_RX_22") (pintype "input"))
    )
    (net (code "21") (name "GATE_C") (class "Default")
      (node (ref "IC10") (pin "2") (pinfunction "I_2") (pintype "input"))
      (node (ref "UC1") (pin "18") (pinfunction "PB0/ADC12_IN8/TIM3_CH3_18") (pintype "bidirectional"))
    )
    (net (code "22") (name "GATE_D") (class "Default")
      (node (ref "IC11") (pin "2") (pinfunction "I_2") (pintype "input"))
      (node (ref "UC1") (pin "19") (pinfunction "PB1/ADC12_IN9/TIM3_CH4_19") (pintype "bidirectional"))
    )
    (net (code "23") (name "GND") (class "Default")
      (node (ref "C1") (pin "-") (pinfunction "-_-") (pintype "passive"))
      (node (ref "C10") (pin "1") (pinfunction "1_1") (pintype "passive"))
      (node (ref "C11") (pin "2") (pinfunction "2_2") (pintype "passive"))
      (node (ref "C12") (pin "-") (pinfunction "-_-") (pintype "passive"))
      (node (ref "C13") (pin "2") (pinfunction "2_2") (pintype "passive"))
      (node (ref "C15") (pin "2") (pinfunction "2_2") (pintype "passive"))
      (node (ref "C17") (pin "2") (pinfunction "2_2") (pintype "passive"))
      (node (ref "C18") (pin "2") (pinfunction "2_2") (pintype "passive"))
      (node (ref "C19") (pin "2") (pinfunction "2_2") (pintype "passive"))
      (node (ref "C2") (pin "2") (pinfunction "2_2") (pintype "passive"))
      (node (ref "C20") (pin "1") (pinfunction "1_1") (pintype "passive"))
      (node (ref "C23") (pin "2") (pinfunction "2_2") (pintype "passive"))
      (node (ref "C24") (pin "2") (pinfunction "2_2") (pintype "passive"))
      (node (ref "C25") (pin "2") (pinfunction "2_2") (pintype "passive"))
      (node (ref "C26") (pin "2") (pinfunction "2_2") (pintype "passive"))
      (node (ref "C27") (pin "2") (pinfunction "2_2") (pintype "passive"))
      (node (ref "C3") (pin "+") (pinfunction "+_+") (pintype "passive"))
      (node (ref "C4") (pin "-") (pinfunction "-_-") (pintype "passive"))
      (node (ref "C5") (pin "2") (pinfunction "2_2") (pintype "passive"))
      (node (ref "C6") (pin "2") (pinfunction "2_2") (pintype "passive"))
      (node (ref "C7") (pin "1") (pinfunction "1_1") (pintype "passive"))
      (node (ref "C8") (pin "2") (pinfunction "2_2") (pintype "passive"))
      (node (ref "C9") (pin "2") (pinfunction "2_2") (pintype "passive"))
      (node (ref "IC1") (pin "1") (pinfunction "GND_1") (pintype "power_in"))
      (node (ref "IC10") (pin "1") (pinfunction "OE_1") (pintype "input"))
      (node (ref "IC10") (pin "3") (pinfunction "GND_3") (pintype "power_in"))
      (node (ref "IC11") (pin "1") (pinfunction "OE_1") (pintype "input"))
      (node (ref "IC11") (pin "3") (pinfunction "GND_3") (pintype "power_in"))
      (node (ref "IC2") (pin "13") (pinfunction "G_13") (pintype "input"))
      (node (ref "IC2") (pin "8") (pinfunction "GND_8") (pintype "power_in"))
      (node (ref "IC3") (pin "13") (pinfunction "G_13") (pintype "input"))
      (node (ref "IC3") (pin "8") (pinfunction "GND_8") (pintype "power_in"))
      (node (ref "IC4") (pin "13") (pinfunction "A0_13") (pintype "input"))
      (node (ref "IC4") (pin "14") (pinfunction "A1_14") (pintype "input"))
      (node (ref "IC4") (pin "15") (pinfunction "ENABLE_15") (pintype "input"))
      (node (ref "IC4") (pin "16") (pinfunction "LDAC_16") (pintype "input"))
      (node (ref "IC4") (pin "5") (pinfunction "VREFL_5") (pintype "bidirectional"))
      (node (ref "IC4") (pin "6") (pinfunction "GND_6") (pintype "power_in"))
      (node (ref "IC5") (pin "4") (pinfunction "GND_4") (pintype "power_in"))
      (node (ref "IC7") (pin "1") (pinfunction "OE_1") (pintype "input"))
      (node (ref "IC7") (pin "3") (pinfunction "GND_3") (pintype "power_in"))
      (node (ref "IC8") (pin "1") (pinfunction "OE_1") (pintype "input"))
      (node (ref "IC8") (pin "3") (pinfunction "GND_3") (pintype "power_in"))
      (node (ref "IC9") (pin "1") (pinfunction "GND_1") (pintype "passive"))
      (node (ref "J1") (pin "GND") (pinfunction "1_GND") (pintype "passive"))
      (node (ref "J1") (pin "GND2") (pinfunction "4_GND2") (pintype "passive"))
      (node (ref "J2") (pin "GND") (pinfunction "1_GND") (pintype "passive"))
      (node (ref "J2") (pin "GND2") (pinfunction "4_GND2") (pintype "passive"))
      (node (ref "J3") (pin "GND") (pinfunction "1_GND") (pintype "passive"))
      (node (ref "J3") (pin "GND2") (pinfunction "4_GND2") (pintype "passive"))
      (node (ref "J4") (pin "GND") (pinfunction "1_GND") (pintype "passive"))
      (node (ref "J4") (pin "GND2") (pinfunction "4_GND2") (pintype "passive"))
      (node (ref "J5") (pin "GND") (pinfunction "1_GND") (pintype "passive"))
      (node (ref "J5") (pin "GND2") (pinfunction "4_GND2") (pintype "passive"))
      (node (ref "J6") (pin "GND") (pinfunction "1_GND") (pintype "passive"))
      (node (ref "J6") (pin "GND2") (pinfunction "4_GND2") (pintype "passive"))
      (node (ref "J7") (pin "GND") (pinfunction "1_GND") (pintype "passive"))
      (node (ref "J7") (pin "GND2") (pinfunction "4_GND2") (pintype "passive"))
      (node (ref "J8") (pin "GND") (pinfunction "1_GND") (pintype "passive"))
      (node (ref "J8") (pin "GND2") (pinfunction "4_GND2") (pintype "passive"))
      (node (ref "JP2") (pin "3") (pinfunction "3_3") (pintype "passive"))
      (node (ref "JP2") (pin "4") (pinfunction "4_4") (pintype "passive"))
      (node (ref "JP2") (pin "5") (pinfunction "5_5") (pintype "passive"))
      (node (ref "JP2") (pin "6") (pinfunction "6_6") (pintype "passive"))
      (node (ref "JP2") (pin "7") (pinfunction "7_7") (pintype "passive"))
      (node (ref "JP2") (pin "8") (pinfunction "8_8") (pintype "passive"))
      (node (ref "JP4") (pin "3") (pinfunction "3_3") (pintype "passive"))
      (node (ref "JP4") (pin "5") (pinfunction "5_5") (pintype "passive"))
      (node (ref "JP4") (pin "9") (pinfunction "9_9") (pintype "passive"))
      (node (ref "LED1") (pin "K") (pinfunction "C_K") (pintype "passive"))
      (node (ref "LED2") (pin "K") (pinfunction "C_K") (pintype "passive"))
      (node (ref "LED3") (pin "K") (pinfunction "C_K") (pintype "passive"))
      (node (ref "LED4") (pin "K") (pinfunction "C_K") (pintype "passive"))
      (node (ref "OK1") (pin "5") (pinfunction "GND_5") (pintype "passive"))
      (node (ref "Q1") (pin "E") (pinfunction "E_E") (pintype "passive"))
      (node (ref "Q2") (pin "E") (pinfunction "E_E") (pintype "passive"))
      (node (ref "R22") (pin "1") (pinfunction "1_1") (pintype "passive"))
      (node (ref "SW1") (pin "C") (pinfunction "C_C") (pintype "passive"))
      (node (ref "SW1") (pin "D") (pinfunction "1_D") (pintype "passive"))
      (node (ref "SW2") (pin "B1") (pinfunction "P_B1") (pintype "passive"))
      (node (ref "SW2") (pin "B2") (pinfunction "P1_B2") (pintype "passive"))
      (node (ref "SW3") (pin "B1") (pinfunction "P_B1") (pintype "passive"))
      (node (ref "SW3") (pin "B2") (pinfunction "P1_B2") (pintype "passive"))
      (node (ref "SW4") (pin "B1") (pinfunction "P_B1") (pintype "passive"))
      (node (ref "SW4") (pin "B2") (pinfunction "P1_B2") (pintype "passive"))
      (node (ref "UC1") (pin "20") (pinfunction "PB2/BOOT1_20") (pintype "bidirectional"))
      (node (ref "UC1") (pin "23") (pinfunction "VSS_1_23") (pintype "power_in"))
      (node (ref "UC1") (pin "35") (pinfunction "VSS_2_35") (pintype "power_in"))
      (node (ref "UC1") (pin "44") (pinfunction "BOOT0_44") (pintype "input"))
      (node (ref "UC1") (pin "47") (pinfunction "VSS_3_47") (pintype "power_in"))
      (node (ref "UC1") (pin "8") (pinfunction "VSS_A_8") (pintype "power_in"))
      (node (ref "X2") (pin "2") (pinfunction "2_2") (pintype "passive"))
    )
    (net (code "24") (name "JTCK") (class "Default")
      (node (ref "JP4") (pin "4") (pinfunction "4_4") (pintype "passive"))
      (node (ref "UC1") (pin "37") (pinfunction "PA14/JTCK/SWCLK_37") (pintype "bidirectional"))
    )
    (net (code "25") (name "JTDI") (class "Default")
      (node (ref "JP4") (pin "8") (pinfunction "8_8") (pintype "passive"))
      (node (ref "UC1") (pin "38") (pinfunction "PA15/JTDI_38") (pintype "bidirectional"))
    )
    (net (code "26") (name "JTDO") (class "Default")
      (node (ref "JP4") (pin "6") (pinfunction "6_6") (pintype "passive"))
      (node (ref "UC1") (pin "39") (pinfunction "PB3/JTDO_39") (pintype "bidirectional"))
    )
    (net (code "27") (name "JTMS") (class "Default")
      (node (ref "JP4") (pin "2") (pinfunction "2_2") (pintype "passive"))
      (node (ref "UC1") (pin "34") (pinfunction "PA13/JTMS/SWDIO_34") (pintype "bidirectional"))
    )
    (net (code "28") (name "LED_1") (class "Default")
      (node (ref "R33") (pin "1") (pinfunction "1_1") (pintype "passive"))
      (node (ref "UC1") (pin "33") (pinfunction "PA12/USART1_RTS/CAN_TX/TIM1_ETR/USBDP_33") (pintype "bidirectional"))
    )
    (net (code "29") (name "LED_2") (class "Default")
      (node (ref "R36") (pin "1") (pinfunction "1_1") (pintype "passive"))
      (node (ref "UC1") (pin "32") (pinfunction "PA11/USART1_CTS/CAN_RX/TIM1_CH4/USBDM_32") (pintype "bidirectional"))
    )
    (net (code "30") (name "LED_3") (class "Default")
      (node (ref "R41") (pin "1") (pinfunction "1_1") (pintype "passive"))
      (node (ref "UC1") (pin "29") (pinfunction "PA8/USART1_CK/TIM1_CH1/MCO_29") (pintype "bidirectional"))
    )
    (net (code "31") (name "LED_4") (class "Default")
      (node (ref "R42") (pin "1") (pinfunction "1_1") (pintype "passive"))
      (node (ref "UC1") (pin "27") (pinfunction "PB14/SPI2_MISO/USART3_RTS/TIM1_CH2N_27") (pintype "input"))
    )
    (net (code "32") (name "MIDI_RX") (class "Default")
      (node (ref "OK1") (pin "6") (pinfunction "VO_6") (pintype "passive"))
      (node (ref "R37") (pin "1") (pinfunction "1_1") (pintype "passive"))
      (node (ref "UC1") (pin "31") (pinfunction "PA10/USART1_RX/TIM1_CH3_31") (pintype "bidirectional"))
    )
    (net (code "33") (name "MIDI_TX") (class "Default")
      (node (ref "R40") (pin "2") (pinfunction "2_2") (pintype "passive"))
      (node (ref "UC1") (pin "30") (pinfunction "PA9/USART1_TX/TIM1_CH2_30") (pintype "input"))
    )
    (net (code "34") (name "Net-(D1-PadA)") (class "Default")
      (node (ref "D1") (pin "A") (pinfunction "A_A") (pintype "passive"))
      (node (ref "JP2") (pin "1") (pinfunction "1_1") (pintype "passive"))
      (node (ref "JP2") (pin "2") (pinfunction "2_2") (pintype "passive"))
    )
    (net (code "35") (name "Net-(D2-PadC)") (class "Default")
      (node (ref "D2") (pin "C") (pinfunction "C_C") (pintype "passive"))
      (node (ref "JP2") (pin "10") (pinfunction "10_10") (pintype "passive"))
      (node (ref "JP2") (pin "9") (pinfunction "9_9") (pintype "passive"))
    )
    (net (code "36") (name "Net-(DISP1-A)") (class "Default")
      (node (ref "DISP1") (pin "12") (pinfunction "A_12") (pintype "passive"))
      (node (ref "R3") (pin "2") (pinfunction "2_2") (pintype "passive"))
    )
    (net (code "37") (name "Net-(DISP1-B)") (class "Default")
      (node (ref "DISP1") (pin "10") (pinfunction "B_10") (pintype "passive"))
      (node (ref "R2") (pin "2") (pinfunction "2_2") (pintype "passive"))
    )
    (net (code "38") (name "Net-(DISP1-C)") (class "Default")
      (node (ref "DISP1") (pin "9") (pinfunction "C_9") (pintype "passive"))
      (node (ref "R10") (pin "2") (pinfunction "2_2") (pintype "passive"))
    )
    (net (code "39") (name "Net-(DISP1-D)") (class "Default")
      (node (ref "DISP1") (pin "7") (pinfunction "D_7") (pintype "passive"))
      (node (ref "R11") (pin "2") (pinfunction "2_2") (pintype "passive"))
    )
    (net (code "40") (name "Net-(DISP1-E)") (class "Default")
      (node (ref "DISP1") (pin "1") (pinfunction "E_1") (pintype "passive"))
      (node (ref "R16") (pin "2") (pinfunction "2_2") (pintype "passive"))
    )
    (net (code "41") (name "Net-(DISP1-F)") (class "Default")
      (node (ref "DISP1") (pin "18") (pinfunction "F_18") (pintype "passive"))
      (node (ref "R8") (pin "2") (pinfunction "2_2") (pintype "passive"))
    )
    (net (code "42") (name "Net-(DISP1-G)") (class "Default")
      (node (ref "DISP1") (pin "17") (pinfunction "G_17") (pintype "passive"))
      (node (ref "R7") (pin "2") (pinfunction "2_2") (pintype "passive"))
    )
    (net (code "43") (name "Net-(DISP1-H)") (class "Default")
      (node (ref "DISP1") (pin "15") (pinfunction "H_15") (pintype "passive"))
      (node (ref "R6") (pin "2") (pinfunction "2_2") (pintype "passive"))
    )
    (net (code "44") (name "Net-(DISP1-J)") (class "Default")
      (node (ref "DISP1") (pin "14") (pinfunction "J_14") (pintype "passive"))
      (node (ref "R5") (pin "2") (pinfunction "2_2") (pintype "passive"))
    )
    (net (code "45") (name "Net-(DISP1-K)") (class "Default")
      (node (ref "DISP1") (pin "6") (pinfunction "K_6") (pintype "passive"))
      (node (ref "R12") (pin "2") (pinfunction "2_2") (pintype "passive"))
    )
    (net (code "46") (name "Net-(DISP1-K1)") (class "Default")
      (node (ref "DISP1") (pin "16") (pinfunction "K1_16") (pintype "passive"))
      (node (ref "Q2") (pin "C") (pinfunction "C_C") (pintype "passive"))
    )
    (net (code "47") (name "Net-(DISP1-K2)") (class "Default")
      (node (ref "DISP1") (pin "11") (pinfunction "K2_11") (pintype "passive"))
      (node (ref "Q1") (pin "C") (pinfunction "C_C") (pintype "passive"))
    )
    (net (code "48") (name "Net-(DISP1-L)") (class "Default")
      (node (ref "DISP1") (pin "5") (pinfunction "L_5") (pintype "passive"))
      (node (ref "R13") (pin "2") (pinfunction "2_2") (pintype "passive"))
    )
    (net (code "49") (name "Net-(DISP1-M)") (class "Default")
      (node (ref "DISP1") (pin "4") (pinfunction "M_4") (pintype "passive"))
      (node (ref "R14") (pin "2") (pinfunction "2_2") (pintype "passive"))
    )
    (net (code "50") (name "Net-(DISP1-N)") (class "Default")
      (node (ref "DISP1") (pin "2") (pinfunction "N_2") (pintype "passive"))
      (node (ref "R15") (pin "2") (pinfunction "2_2") (pintype "passive"))
    )
    (net (code "51") (name "Net-(DISP1-P)") (class "Default")
      (node (ref "DISP1") (pin "13") (pinfunction "P_13") (pintype "passive"))
      (node (ref "R4") (pin "2") (pinfunction "2_2") (pintype "passive"))
    )
    (net (code "52") (name "Net-(IC2A-QA)") (class "Default")
      (node (ref "IC2") (pin "15") (pinfunction "QA_15") (pintype "tri_state"))
      (node (ref "R3") (pin "1") (pinfunction "1_1") (pintype "passive"))
    )
    (net (code "53") (name "Net-(IC2A-QB)") (class "Default")
      (node (ref "IC2") (pin "1") (pinfunction "QB_1") (pintype "tri_state"))
      (node (ref "R2") (pin "1") (pinfunction "1_1") (pintype "passive"))
    )
    (net (code "54") (name "Net-(IC2A-QC)") (class "Default")
      (node (ref "IC2") (pin "2") (pinfunction "QC_2") (pintype "tri_state"))
      (node (ref "R10") (pin "1") (pinfunction "1_1") (pintype "passive"))
    )
    (net (code "55") (name "Net-(IC2A-QD)") (class "Default")
      (node (ref "IC2") (pin "3") (pinfunction "QD_3") (pintype "tri_state"))
      (node (ref "R11") (pin "1") (pinfunction "1_1") (pintype "passive"))
    )
    (net (code "56") (name "Net-(IC2A-QE)") (class "Default")
      (node (ref "IC2") (pin "4") (pinfunction "QE_4") (pintype "tri_state"))
      (node (ref "R16") (pin "1") (pinfunction "1_1") (pintype "passive"))
    )
    (net (code "57") (name "Net-(IC2A-QF)") (class "Default")
      (node (ref "IC2") (pin "5") (pinfunction "QF_5") (pintype "tri_state"))
      (node (ref "R8") (pin "1") (pinfunction "1_1") (pintype "passive"))
    )
    (net (code "58") (name "Net-(IC2A-QG)") (class "Default")
      (node (ref "IC2") (pin "6") (pinfunction "QG_6") (pintype "tri_state"))
      (node (ref "R7") (pin "1") (pinfunction "1_1") (pintype "passive"))
    )
    (net (code "59") (name "Net-(IC2A-QH)") (class "Default")
      (node (ref "IC2") (pin "7") (pinfunction "QH_7") (pintype "tri_state"))
      (node (ref "R6") (pin "1") (pinfunction "1_1") (pintype "passive"))
    )
    (net (code "60") (name "Net-(IC2A-QH*)") (class "Default")
      (node (ref "IC2") (pin "9") (pinfunction "QH*_9") (pintype "tri_state"))
      (node (ref "IC3") (pin "14") (pinfunction "SER_14") (pintype "input"))
    )
    (net (code "61") (name "Net-(IC3A-QA)") (class "Default")
      (node (ref "IC3") (pin "15") (pinfunction "QA_15") (pintype "tri_state"))
      (node (ref "R5") (pin "1") (pinfunction "1_1") (pintype "passive"))
    )
    (net (code "62") (name "Net-(IC3A-QB)") (class "Default")
      (node (ref "IC3") (pin "1") (pinfunction "QB_1") (pintype "tri_state"))
      (node (ref "R12") (pin "1") (pinfunction "1_1") (pintype "passive"))
    )
    (net (code "63") (name "Net-(IC3A-QC)") (class "Default")
      (node (ref "IC3") (pin "2") (pinfunction "QC_2") (pintype "tri_state"))
      (node (ref "R13") (pin "1") (pinfunction "1_1") (pintype "passive"))
    )
    (net (code "64") (name "Net-(IC3A-QD)") (class "Default")
      (node (ref "IC3") (pin "3") (pinfunction "QD_3") (pintype "tri_state"))
      (node (ref "R14") (pin "1") (pinfunction "1_1") (pintype "passive"))
    )
    (net (code "65") (name "Net-(IC3A-QE)") (class "Default")
      (node (ref "IC3") (pin "4") (pinfunction "QE_4") (pintype "tri_state"))
      (node (ref "R15") (pin "1") (pinfunction "1_1") (pintype "passive"))
    )
    (net (code "66") (name "Net-(IC3A-QF)") (class "Default")
      (node (ref "IC3") (pin "5") (pinfunction "QF_5") (pintype "tri_state"))
      (node (ref "R4") (pin "1") (pinfunction "1_1") (pintype "passive"))
    )
    (net (code "67") (name "Net-(IC6A--IN)") (class "Default")
      (node (ref "C14") (pin "1") (pinfunction "1_1") (pintype "passive"))
      (node (ref "IC6") (pin "2") (pinfunction "-IN_2") (pintype "input"))
      (node (ref "R18") (pin "1") (pinfunction "1_1") (pintype "passive"))
      (node (ref "R26") (pin "2") (pinfunction "2_2") (pintype "passive"))
    )
    (net (code "68") (name "Net-(IC6A-OUT)") (class "Default")
      (node (ref "C14") (pin "2") (pinfunction "2_2") (pintype "passive"))
      (node (ref "IC6") (pin "1") (pinfunction "OUT_1") (pintype "output"))
      (node (ref "R24") (pin "2") (pinfunction "2_2") (pintype "passive"))
    )
    (net (code "69") (name "Net-(IC6B--IN)") (class "Default")
      (node (ref "C21") (pin "1") (pinfunction "1_1") (pintype "passive"))
      (node (ref "IC6") (pin "6") (pinfunction "-IN_6") (pintype "input"))
      (node (ref "R19") (pin "1") (pinfunction "1_1") (pintype "passive"))
      (node (ref "R28") (pin "2") (pinfunction "2_2") (pintype "passive"))
    )
    (net (code "70") (name "Net-(IC6B-OUT)") (class "Default")
      (node (ref "C21") (pin "2") (pinfunction "2_2") (pintype "passive"))
      (node (ref "IC6") (pin "7") (pinfunction "OUT_7") (pintype "output"))
      (node (ref "R30") (pin "2") (pinfunction "2_2") (pintype "passive"))
    )
    (net (code "71") (name "Net-(IC6C--IN)") (class "Default")
      (node (ref "C22") (pin "1") (pinfunction "1_1") (pintype "passive"))
      (node (ref "IC6") (pin "9") (pinfunction "-IN_9") (pintype "input"))
      (node (ref "R20") (pin "1") (pinfunction "1_1") (pintype "passive"))
      (node (ref "R29") (pin "2") (pinfunction "2_2") (pintype "passive"))
    )
    (net (code "72") (name "Net-(IC6C-OUT)") (class "Default")
      (node (ref "C22") (pin "2") (pinfunction "2_2") (pintype "passive"))
      (node (ref "IC6") (pin "8") (pinfunction "OUT_8") (pintype "output"))
      (node (ref "R31") (pin "2") (pinfunction "2_2") (pintype "passive"))
    )
    (net (code "73") (name "Net-(IC6D--IN)") (class "Default")
      (node (ref "C16") (pin "1") (pinfunction "1_1") (pintype "passive"))
      (node (ref "IC6") (pin "13") (pinfunction "-IN_13") (pintype "input"))
      (node (ref "R21") (pin "1") (pinfunction "1_1") (pintype "passive"))
      (node (ref "R27") (pin "2") (pinfunction "2_2") (pintype "passive"))
    )
    (net (code "74") (name "Net-(IC6D-OUT)") (class "Default")
      (node (ref "C16") (pin "2") (pinfunction "2_2") (pintype "passive"))
      (node (ref "IC6") (pin "14") (pinfunction "OUT_14") (pintype "output"))
      (node (ref "R25") (pin "2") (pinfunction "2_2") (pintype "passive"))
    )
    (net (code "75") (name "Net-(IC7A-O)") (class "Default")
      (node (ref "IC7") (pin "4") (pinfunction "O_4") (pintype "tri_state"))
      (node (ref "R32") (pin "2") (pinfunction "2_2") (pintype "passive"))
    )
    (net (code "76") (name "Net-(IC8A-O)") (class "Default")
      (node (ref "IC8") (pin "4") (pinfunction "O_4") (pintype "tri_state"))
      (node (ref "R34") (pin "2") (pinfunction "2_2") (pintype "passive"))
    )
    (net (code "77") (name "Net-(IC10A-O)") (class "Default")
      (node (ref "IC10") (pin "4") (pinfunction "O_4") (pintype "tri_state"))
      (node (ref "R38") (pin "2") (pinfunction "2_2") (pintype "passive"))
    )
    (net (code "78") (name "Net-(IC11A-O)") (class "Default")
      (node (ref "IC11") (pin "4") (pinfunction "O_4") (pintype "tri_state"))
      (node (ref "R43") (pin "2") (pinfunction "2_2") (pintype "passive"))
    )
    (net (code "79") (name "Net-(J1-2)") (class "Default")
      (node (ref "J1") (pin "TIP") (pinfunction "2_TIP") (pintype "passive"))
      (node (ref "R25") (pin "1") (pinfunction "1_1") (pintype "passive"))
      (node (ref "R27") (pin "1") (pinfunction "1_1") (pintype "passive"))
    )
    (net (code "80") (name "Net-(J2-2)") (class "Default")
      (node (ref "J2") (pin "TIP") (pinfunction "2_TIP") (pintype "passive"))
      (node (ref "R32") (pin "1") (pinfunction "1_1") (pintype "passive"))
    )
    (net (code "81") (name "Net-(J3-2)") (class "Default")
      (node (ref "J3") (pin "TIP") (pinfunction "2_TIP") (pintype "passive"))
      (node (ref "R29") (pin "1") (pinfunction "1_1") (pintype "passive"))
      (node (ref "R31") (pin "1") (pinfunction "1_1") (pintype "passive"))
    )
    (net (code "82") (name "Net-(J4-2)") (class "Default")
      (node (ref "J4") (pin "TIP") (pinfunction "2_TIP") (pintype "passive"))
      (node (ref "R34") (pin "1") (pinfunction "1_1") (pintype "passive"))
    )
    (net (code "83") (name "Net-(J5-2)") (class "Default")
      (node (ref "J5") (pin "TIP") (pinfunction "2_TIP") (pintype "passive"))
      (node (ref "R28") (pin "1") (pinfunction "1_1") (pintype "passive"))
      (node (ref "R30") (pin "1") (pinfunction "1_1") (pintype "passive"))
    )
    (net (code "84") (name "Net-(J6-2)") (class "Default")
      (node (ref "J6") (pin "TIP") (pinfunction "2_TIP") (pintype "passive"))
      (node (ref "R38") (pin "1") (pinfunction "1_1") (pintype "passive"))
    )
    (net (code "85") (name "Net-(J7-2)") (class "Default")
      (node (ref "J7") (pin "TIP") (pinfunction "2_TIP") (pintype "passive"))
      (node (ref "R24") (pin "1") (pinfunction "1_1") (pintype "passive"))
      (node (ref "R26") (pin "1") (pinfunction "1_1") (pintype "passive"))
    )
    (net (code "86") (name "Net-(J8-2)") (class "Default")
      (node (ref "J8") (pin "TIP") (pinfunction "2_TIP") (pintype "passive"))
      (node (ref "R43") (pin "1") (pinfunction "1_1") (pintype "passive"))
    )
    (net (code "87") (name "Net-(LED1-PadA)") (class "Default")
      (node (ref "LED1") (pin "A") (pinfunction "A_A") (pintype "passive"))
      (node (ref "R33") (pin "2") (pinfunction "2_2") (pintype "passive"))
    )
    (net (code "88") (name "Net-(LED2-PadA)") (class "Default")
      (node (ref "LED2") (pin "A") (pinfunction "A_A") (pintype "passive"))
      (node (ref "R36") (pin "2") (pinfunction "2_2") (pintype "passive"))
    )
    (net (code "89") (name "Net-(LED3-PadA)") (class "Default")
      (node (ref "LED3") (pin "A") (pinfunction "A_A") (pintype "passive"))
      (node (ref "R41") (pin "2") (pinfunction "2_2") (pintype "passive"))
    )
    (net (code "90") (name "Net-(LED4-PadA)") (class "Default")
      (node (ref "LED4") (pin "A") (pinfunction "A_A") (pintype "passive"))
      (node (ref "R42") (pin "2") (pinfunction "2_2") (pintype "passive"))
    )
    (net (code "91") (name "Net-(OK1-A)") (class "Default")
      (node (ref "D3") (pin "C") (pinfunction "C_C") (pintype "passive"))
      (node (ref "OK1") (pin "2") (pinfunction "A_2") (pintype "passive"))
      (node (ref "R35") (pin "1") (pinfunction "1_1") (pintype "passive"))
    )
    (net (code "92") (name "Net-(OK1-C)") (class "Default")
      (node (ref "D3") (pin "A") (pinfunction "A_A") (pintype "passive"))
      (node (ref "OK1") (pin "3") (pinfunction "C_3") (pintype "passive"))
      (node (ref "X1") (pin "5") (pinfunction "5_5") (pintype "passive"))
    )
    (net (code "93") (name "Net-(Q1-PadB)") (class "Default")
      (node (ref "Q1") (pin "B") (pinfunction "B_B") (pintype "passive"))
      (node (ref "R1") (pin "2") (pinfunction "2_2") (pintype "passive"))
    )
    (net (code "94") (name "Net-(Q2-PadB)") (class "Default")
      (node (ref "Q2") (pin "B") (pinfunction "B_B") (pintype "passive"))
      (node (ref "R9") (pin "2") (pinfunction "2_2") (pintype "passive"))
    )
    (net (code "95") (name "Net-(R35-Pad2)") (class "Default")
      (node (ref "R35") (pin "2") (pinfunction "2_2") (pintype "passive"))
      (node (ref "X1") (pin "4") (pinfunction "4_4") (pintype "passive"))
    )
    (net (code "96") (name "Net-(R39-Pad1)") (class "Default")
      (node (ref "R39") (pin "1") (pinfunction "1_1") (pintype "passive"))
      (node (ref "X2") (pin "4") (pinfunction "4_4") (pintype "passive"))
    )
    (net (code "97") (name "Net-(R40-Pad1)") (class "Default")
      (node (ref "R40") (pin "1") (pinfunction "1_1") (pintype "passive"))
      (node (ref "X2") (pin "5") (pinfunction "5_5") (pintype "passive"))
    )
    (net (code "98") (name "Net-(UC1-PD0-OSC_IN)") (class "Default")
      (node (ref "C7") (pin "2") (pinfunction "2_2") (pintype "passive"))
      (node (ref "Q3") (pin "2") (pinfunction "2_2") (pintype "passive"))
      (node (ref "UC1") (pin "5") (pinfunction "PD0-OSC_IN_5") (pintype "input"))
    )
    (net (code "99") (name "Net-(UC1-PD1-OSC_OUT)") (class "Default")
      (node (ref "C10") (pin "2") (pinfunction "2_2") (pintype "passive"))
      (node (ref "Q3") (pin "1") (pinfunction "1_1") (pintype "passive"))
      (node (ref "UC1") (pin "6") (pinfunction "PD1-OSC_OUT_6") (pintype "input"))
    )
    (net (code "100") (name "RESET") (class "Default")
      (node (ref "JP4") (pin "10") (pinfunction "10_10") (pintype "passive"))
      (node (ref "R17") (pin "1") (pinfunction "1_1") (pintype "passive"))
      (node (ref "UC1") (pin "7") (pinfunction "NRST_7") (pintype "input"))
    )
    (net (code "101") (name "SWITCH_0") (class "Default")
      (node (ref "SW2") (pin "A1") (pinfunction "S_A1") (pintype "passive"))
      (node (ref "SW2") (pin "A2") (pinfunction "S1_A2") (pintype "passive"))
      (node (ref "UC1") (pin "15") (pinfunction "PA5/SPI1_SCK/ADC12_IN5_15") (pintype "bidirectional"))
    )
    (net (code "102") (name "SWITCH_1") (class "Default")
      (node (ref "SW3") (pin "A1") (pinfunction "S_A1") (pintype "passive"))
      (node (ref "SW3") (pin "A2") (pinfunction "S1_A2") (pintype "passive"))
      (node (ref "UC1") (pin "16") (pinfunction "PA6/SPI1_MISO/ADC12_IN6/TIM3_CH1_16") (pintype "bidirectional"))
    )
    (net (code "103") (name "SWITCH_2") (class "Default")
      (node (ref "SW4") (pin "A1") (pinfunction "S_A1") (pintype "passive"))
      (node (ref "SW4") (pin "A2") (pinfunction "S1_A2") (pintype "passive"))
      (node (ref "UC1") (pin "14") (pinfunction "PA4/SPI1_NSS/USART2_CK/ADC12_IN4_14") (pintype "bidirectional"))
    )
    (net (code "104") (name "VCC") (class "Default")
      (node (ref "C1") (pin "+") (pinfunction "+_+") (pintype "passive"))
      (node (ref "C12") (pin "+") (pinfunction "+_+") (pintype "passive"))
      (node (ref "C19") (pin "1") (pinfunction "1_1") (pintype "passive"))
      (node (ref "C25") (pin "1") (pinfunction "1_1") (pintype "passive"))
      (node (ref "D1") (pin "C") (pinfunction "C_C") (pintype "passive"))
      (node (ref "IC1") (pin "3") (pinfunction "VIN_3") (pintype "input"))
      (node (ref "IC5") (pin "2") (pinfunction "V+_2") (pintype "power_in"))
      (node (ref "IC6") (pin "4") (pinfunction "V+_4") (pintype "power_in"))
      (node (ref "IC9") (pin "3") (pinfunction "VI_3") (pintype "input"))
    )
    (net (code "105") (name "VEE") (class "Default")
      (node (ref "C20") (pin "2") (pinfunction "2_2") (pintype "passive"))
      (node (ref "C3") (pin "-") (pinfunction "-_-") (pintype "passive"))
      (node (ref "D2") (pin "A") (pinfunction "A_A") (pintype "passive"))
      (node (ref "IC6") (pin "11") (pinfunction "V-_11") (pintype "power_in"))
    )
    (net (code "106") (name "VREF") (class "Default")
      (node (ref "C17") (pin "1") (pinfunction "1_1") (pintype "passive"))
      (node (ref "IC4") (pin "3") (pinfunction "VREFH_3") (pintype "bidirectional"))
      (node (ref "R23") (pin "2") (pinfunction "2_2") (pintype "passive"))
    )
    (net (code "107") (name "VREF{slash}2") (class "Default")
      (node (ref "IC6") (pin "10") (pinfunction "+IN_10") (pintype "input"))
      (node (ref "IC6") (pin "12") (pinfunction "+IN_12") (pintype "input"))
      (node (ref "IC6") (pin "3") (pinfunction "+IN_3") (pintype "input"))
      (node (ref "IC6") (pin "5") (pinfunction "+IN_5") (pintype "input"))
      (node (ref "R22") (pin "2") (pinfunction "2_2") (pintype "passive"))
      (node (ref "R23") (pin "1") (pinfunction "1_1") (pintype "passive"))
    )
    (net (code "108") (name "unconnected-(DISP1-DP-Pad8)") (class "Default")
      (node (ref "DISP1") (pin "8") (pinfunction "DP_8") (pintype "passive"))
    )
    (net (code "109") (name "unconnected-(IC3A-QG-Pad6)") (class "Default")
      (node (ref "IC3") (pin "6") (pinfunction "QG_6") (pintype "tri_state"))
    )
    (net (code "110") (name "unconnected-(IC3A-QH*-Pad9)") (class "Default")
      (node (ref "IC3") (pin "9") (pinfunction "QH*_9") (pintype "tri_state"))
    )
    (net (code "111") (name "unconnected-(IC3A-QH-Pad7)") (class "Default")
      (node (ref "IC3") (pin "7") (pinfunction "QH_7") (pintype "tri_state"))
    )
    (net (code "112") (name "unconnected-(IC5-OPT-Pad3)") (class "Default")
      (node (ref "IC5") (pin "3") (pinfunction "OPT_3") (pintype "output"))
    )
    (net (code "113") (name "unconnected-(IC5-TRM-Pad5)") (class "Default")
      (node (ref "IC5") (pin "5") (pinfunction "TRM_5") (pintype "input"))
    )
    (net (code "114") (name "unconnected-(J1-3-PadSW)") (class "Default")
      (node (ref "J1") (pin "SW") (pinfunction "3_SW") (pintype "passive"))
    )
    (net (code "115") (name "unconnected-(J2-3-PadSW)") (class "Default")
      (node (ref "J2") (pin "SW") (pinfunction "3_SW") (pintype "passive"))
    )
    (net (code "116") (name "unconnected-(J3-3-PadSW)") (class "Default")
      (node (ref "J3") (pin "SW") (pinfunction "3_SW") (pintype "passive"))
    )
    (net (code "117") (name "unconnected-(J4-3-PadSW)") (class "Default")
      (node (ref "J4") (pin "SW") (pinfunction "3_SW") (pintype "passive"))
    )
    (net (code "118") (name "unconnected-(J5-3-PadSW)") (class "Default")
      (node (ref "J5") (pin "SW") (pinfunction "3_SW") (pintype "passive"))
    )
    (net (code "119") (name "unconnected-(J6-3-PadSW)") (class "Default")
      (node (ref "J6") (pin "SW") (pinfunction "3_SW") (pintype "passive"))
    )
    (net (code "120") (name "unconnected-(J7-3-PadSW)") (class "Default")
      (node (ref "J7") (pin "SW") (pinfunction "3_SW") (pintype "passive"))
    )
    (net (code "121") (name "unconnected-(J8-3-PadSW)") (class "Default")
      (node (ref "J8") (pin "SW") (pinfunction "3_SW") (pintype "passive"))
    )
    (net (code "122") (name "unconnected-(JP4-Pad7)") (class "Default")
      (node (ref "JP4") (pin "7") (pinfunction "7_7") (pintype "passive"))
    )
    (net (code "123") (name "unconnected-(OK1-VE-Pad7)") (class "Default")
      (node (ref "OK1") (pin "7") (pinfunction "VE_7") (pintype "passive"))
    )
    (net (code "124") (name "unconnected-(UC1-PA0_WKUP{slash}USART2_CTS{slash}ADC12_IN0{slash}TIM2_CH1_ETR-Pad10)") (class "Default")
      (node (ref "UC1") (pin "10") (pinfunction "PA0_WKUP/USART2_CTS/ADC12_IN0/TIM2_CH1_ETR_10") (pintype "bidirectional"))
    )
    (net (code "125") (name "unconnected-(UC1-PA1{slash}USART2_RTS{slash}ADC12_IN1{slash}TIM2_CH2-Pad11)") (class "Default")
      (node (ref "UC1") (pin "11") (pinfunction "PA1/USART2_RTS/ADC12_IN1/TIM2_CH2_11") (pintype "bidirectional"))
    )
    (net (code "126") (name "unconnected-(UC1-PA2{slash}USART2_TX{slash}ADC12_IN2{slash}TIM2_CH3-Pad12)") (class "Default")
      (node (ref "UC1") (pin "12") (pinfunction "PA2/USART2_TX/ADC12_IN2/TIM2_CH3_12") (pintype "bidirectional"))
    )
    (net (code "127") (name "unconnected-(UC1-PA3{slash}USART2_RX{slash}ADC12_IN3{slash}TIM2_CH4-Pad13)") (class "Default")
      (node (ref "UC1") (pin "13") (pinfunction "PA3/USART2_RX/ADC12_IN3/TIM2_CH4_13") (pintype "bidirectional"))
    )
    (net (code "128") (name "unconnected-(UC1-PA7{slash}SPI1_MOSI{slash}ADC12_IN7{slash}TIM3_CH2-Pad17)") (class "Default")
      (node (ref "UC1") (pin "17") (pinfunction "PA7/SPI1_MOSI/ADC12_IN7/TIM3_CH2_17") (pintype "bidirectional"))
    )
    (net (code "129") (name "unconnected-(UC1-PB4{slash}NJTRST-Pad40)") (class "Default")
      (node (ref "UC1") (pin "40") (pinfunction "PB4/NJTRST_40") (pintype "bidirectional"))
    )
    (net (code "130") (name "unconnected-(X1-Pad1)") (class "Default")
      (node (ref "X1") (pin "1") (pinfunction "1_1") (pintype "passive"))
    )
    (net (code "131") (name "unconnected-(X1-Pad2)") (class "Default")
      (node (ref "X1") (pin "2") (pinfunction "2_2") (pintype "passive"))
    )
    (net (code "132") (name "unconnected-(X1-Pad3)") (class "Default")
      (node (ref "X1") (pin "3") (pinfunction "3_3") (pintype "passive"))
    )
    (net (code "133") (name "unconnected-(X2-Pad1)") (class "Default")
      (node (ref "X2") (pin "1") (pinfunction "1_1") (pintype "passive"))
    )
    (net (code "134") (name "unconnected-(X2-Pad3)") (class "Default")
      (node (ref "X2") (pin "3") (pinfunction "3_3") (pintype "passive"))
    )
  )
)
